# Motor_Driver.net
KiCad netlist of a schematic drawn in EAGLE
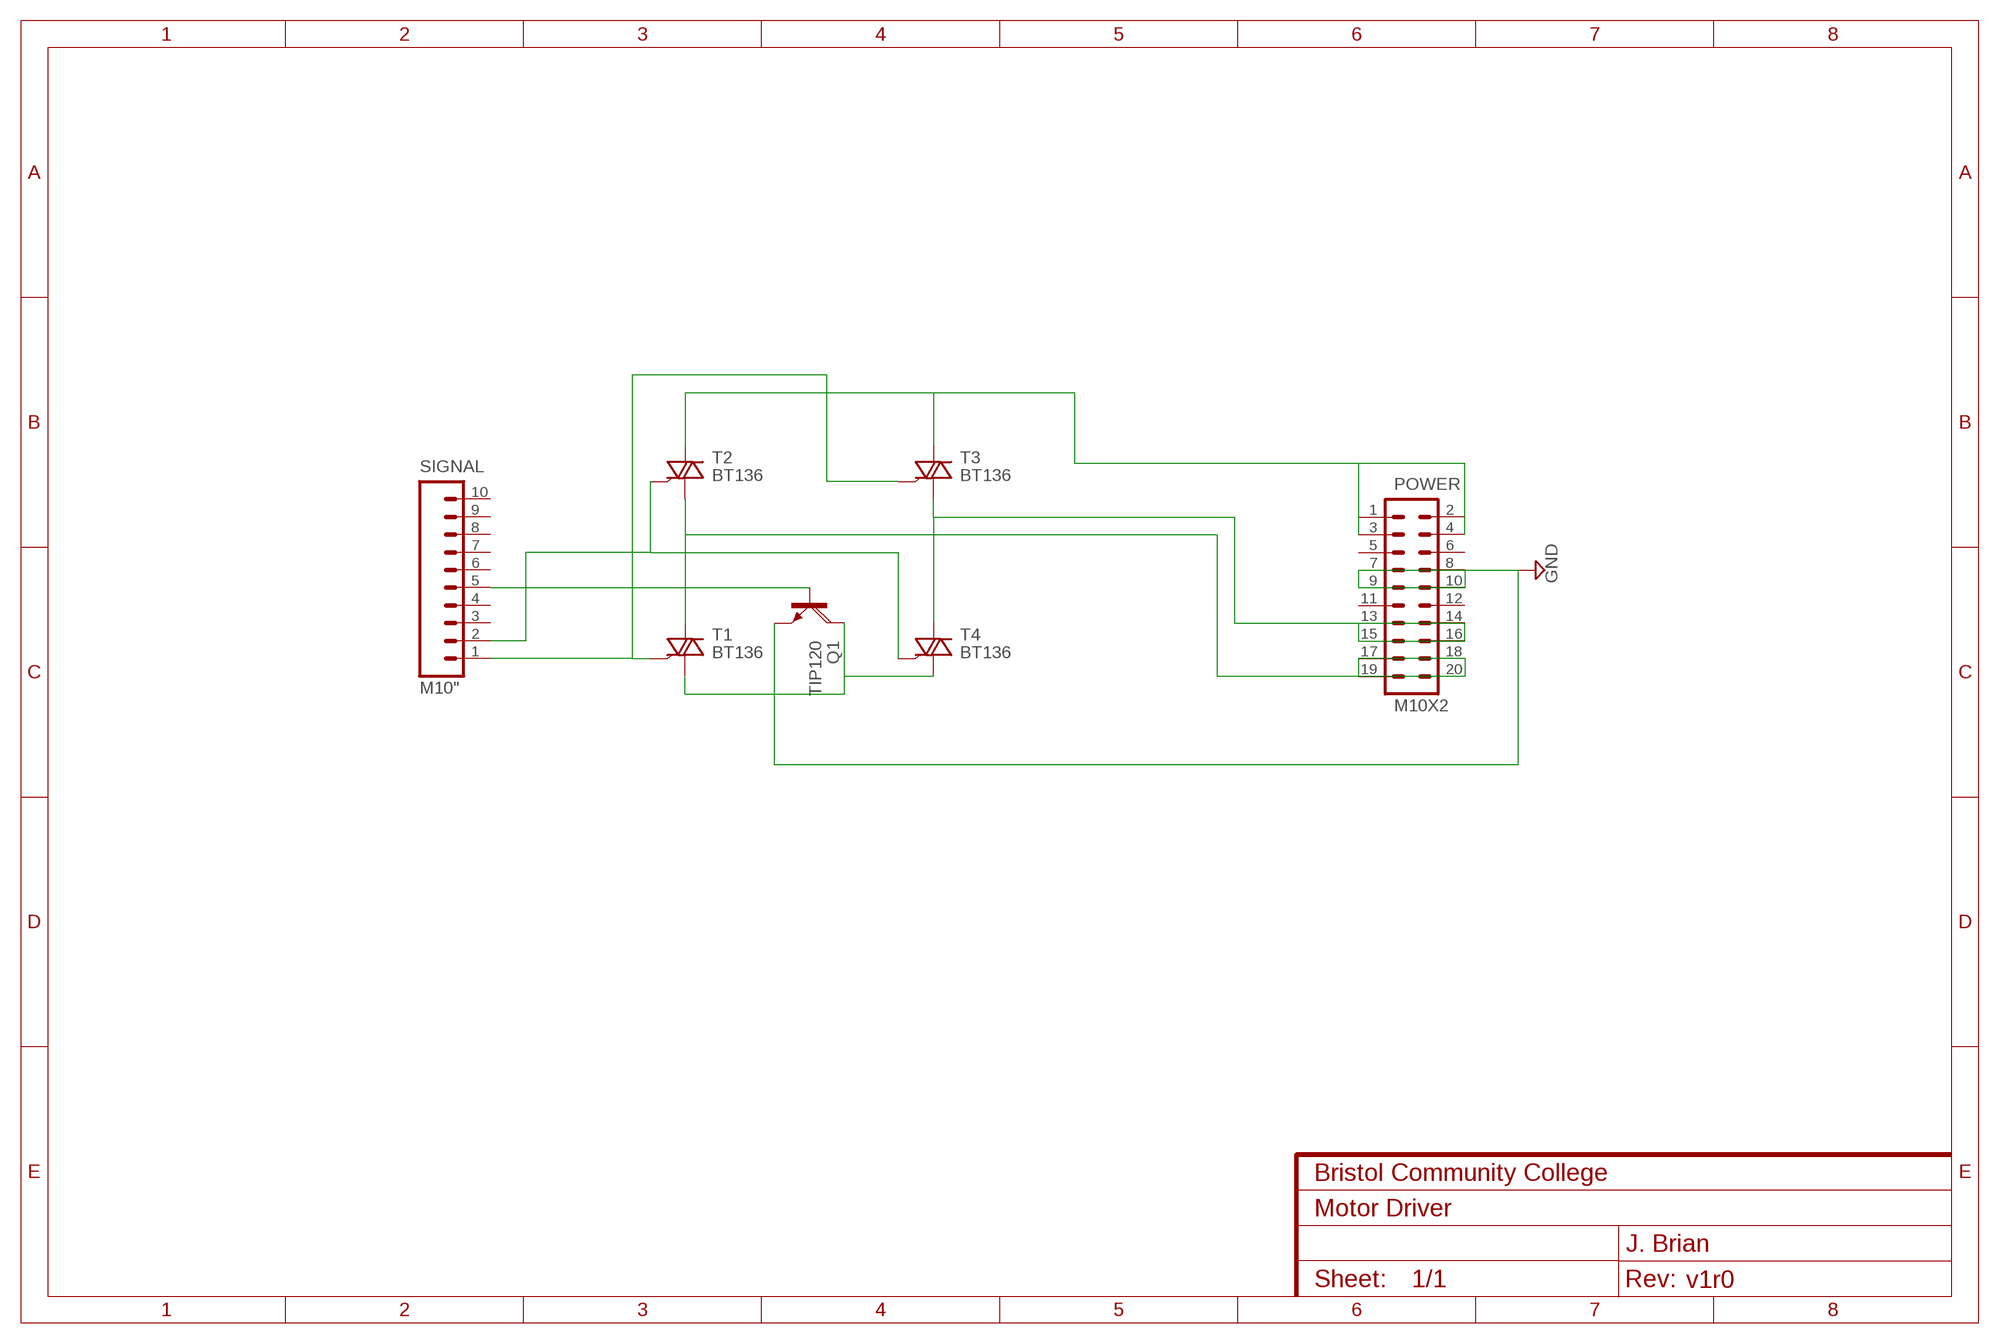
[diagram p0: schematic, sheet 1]

(export (version "E")
  (design (tool "Eeschema 10.0.6"))
  (components
    (comp (ref "POWER")
      (value "M10X2")
      (footprint "eagle-import:2X10")
      (libsource (lib "eagle-import") (part "M10X2"))
    )
    (comp (ref "Q1")
      (value "TIP120")
      (footprint "eagle-import:TO220AH")
      (libsource (lib "eagle-import") (part "TIP120"))
    )
    (comp (ref "SIGNAL")
      (value "M10\"")
      (footprint "eagle-import:1X10")
      (libsource (lib "eagle-import") (part "M10{dblquote}"))
    )
    (comp (ref "T1")
      (value "BT136")
      (footprint "eagle-import:TO220AB")
      (libsource (lib "eagle-import") (part "BT136"))
    )
    (comp (ref "T2")
      (value "BT136")
      (footprint "eagle-import:TO220AB")
      (libsource (lib "eagle-import") (part "BT136"))
    )
    (comp (ref "T3")
      (value "BT136")
      (footprint "eagle-import:TO220AB")
      (libsource (lib "eagle-import") (part "BT136"))
    )
    (comp (ref "T4")
      (value "BT136")
      (footprint "eagle-import:TO220AB")
      (libsource (lib "eagle-import") (part "BT136"))
    )
  )
  (nets
    (net (code "1") (name "GND") (class "Default")
      (node (ref "POWER") (pin "10") (pinfunction "10_10") (pintype "passive"))
      (node (ref "POWER") (pin "7") (pinfunction "7_7") (pintype "passive"))
      (node (ref "POWER") (pin "8") (pinfunction "8_8") (pintype "passive"))
      (node (ref "POWER") (pin "9") (pinfunction "9_9") (pintype "passive"))
      (node (ref "Q1") (pin "E") (pinfunction "E_E") (pintype "passive"))
    )
    (net (code "2") (name "Net-(Q1-PadB)") (class "Default")
      (node (ref "Q1") (pin "B") (pinfunction "B_B") (pintype "passive"))
      (node (ref "SIGNAL") (pin "5") (pinfunction "5_5") (pintype "passive"))
    )
    (net (code "3") (name "Net-(T1-A1)") (class "Default")
      (node (ref "Q1") (pin "C") (pinfunction "C_C") (pintype "passive"))
      (node (ref "T1") (pin "1") (pinfunction "A1_1") (pintype "passive"))
      (node (ref "T4") (pin "1") (pinfunction "A1_1") (pintype "passive"))
    )
    (net (code "4") (name "Net-(T1-A2)") (class "Default")
      (node (ref "POWER") (pin "17") (pinfunction "17_17") (pintype "passive"))
      (node (ref "POWER") (pin "18") (pinfunction "18_18") (pintype "passive"))
      (node (ref "POWER") (pin "19") (pinfunction "19_19") (pintype "passive"))
      (node (ref "POWER") (pin "20") (pinfunction "20_20") (pintype "passive"))
      (node (ref "T1") (pin "2") (pinfunction "A2_2") (pintype "passive"))
      (node (ref "T2") (pin "1") (pinfunction "A1_1") (pintype "passive"))
    )
    (net (code "5") (name "Net-(T1-G)") (class "Default")
      (node (ref "SIGNAL") (pin "1") (pinfunction "1_1") (pintype "passive"))
      (node (ref "T1") (pin "3") (pinfunction "G_3") (pintype "passive"))
      (node (ref "T3") (pin "3") (pinfunction "G_3") (pintype "passive"))
    )
    (net (code "6") (name "Net-(T2-A2)") (class "Default")
      (node (ref "POWER") (pin "1") (pinfunction "1_1") (pintype "passive"))
      (node (ref "POWER") (pin "2") (pinfunction "2_2") (pintype "passive"))
      (node (ref "POWER") (pin "3") (pinfunction "3_3") (pintype "passive"))
      (node (ref "POWER") (pin "4") (pinfunction "4_4") (pintype "passive"))
      (node (ref "T2") (pin "2") (pinfunction "A2_2") (pintype "passive"))
      (node (ref "T3") (pin "2") (pinfunction "A2_2") (pintype "passive"))
    )
    (net (code "7") (name "Net-(T2-G)") (class "Default")
      (node (ref "SIGNAL") (pin "2") (pinfunction "2_2") (pintype "passive"))
      (node (ref "T2") (pin "3") (pinfunction "G_3") (pintype "passive"))
      (node (ref "T4") (pin "3") (pinfunction "G_3") (pintype "passive"))
    )
    (net (code "8") (name "Net-(T3-A1)") (class "Default")
      (node (ref "POWER") (pin "13") (pinfunction "13_13") (pintype "passive"))
      (node (ref "POWER") (pin "14") (pinfunction "14_14") (pintype "passive"))
      (node (ref "POWER") (pin "15") (pinfunction "15_15") (pintype "passive"))
      (node (ref "POWER") (pin "16") (pinfunction "16_16") (pintype "passive"))
      (node (ref "T3") (pin "1") (pinfunction "A1_1") (pintype "passive"))
      (node (ref "T4") (pin "2") (pinfunction "A2_2") (pintype "passive"))
    )
    (net (code "9") (name "unconnected-(POWER-Pad5)") (class "Default")
      (node (ref "POWER") (pin "5") (pinfunction "5_5") (pintype "passive"))
    )
    (net (code "10") (name "unconnected-(POWER-Pad6)") (class "Default")
      (node (ref "POWER") (pin "6") (pinfunction "6_6") (pintype "passive"))
    )
    (net (code "11") (name "unconnected-(POWER-Pad11)") (class "Default")
      (node (ref "POWER") (pin "11") (pinfunction "11_11") (pintype "passive"))
    )
    (net (code "12") (name "unconnected-(POWER-Pad12)") (class "Default")
      (node (ref "POWER") (pin "12") (pinfunction "12_12") (pintype "passive"))
    )
    (net (code "13") (name "unconnected-(SIGNAL-Pad3)") (class "Default")
      (node (ref "SIGNAL") (pin "3") (pinfunction "3_3") (pintype "passive"))
    )
    (net (code "14") (name "unconnected-(SIGNAL-Pad4)") (class "Default")
      (node (ref "SIGNAL") (pin "4") (pinfunction "4_4") (pintype "passive"))
    )
    (net (code "15") (name "unconnected-(SIGNAL-Pad6)") (class "Default")
      (node (ref "SIGNAL") (pin "6") (pinfunction "6_6") (pintype "passive"))
    )
    (net (code "16") (name "unconnected-(SIGNAL-Pad7)") (class "Default")
      (node (ref "SIGNAL") (pin "7") (pinfunction "7_7") (pintype "passive"))
    )
    (net (code "17") (name "unconnected-(SIGNAL-Pad8)") (class "Default")
      (node (ref "SIGNAL") (pin "8") (pinfunction "8_8") (pintype "passive"))
    )
    (net (code "18") (name "unconnected-(SIGNAL-Pad9)") (class "Default")
      (node (ref "SIGNAL") (pin "9") (pinfunction "9_9") (pintype "passive"))
    )
    (net (code "19") (name "unconnected-(SIGNAL-Pad10)") (class "Default")
      (node (ref "SIGNAL") (pin "10") (pinfunction "10_10") (pintype "passive"))
    )
  )
)
